# esp32.net
KiCad netlist of a schematic drawn in Altium Designer
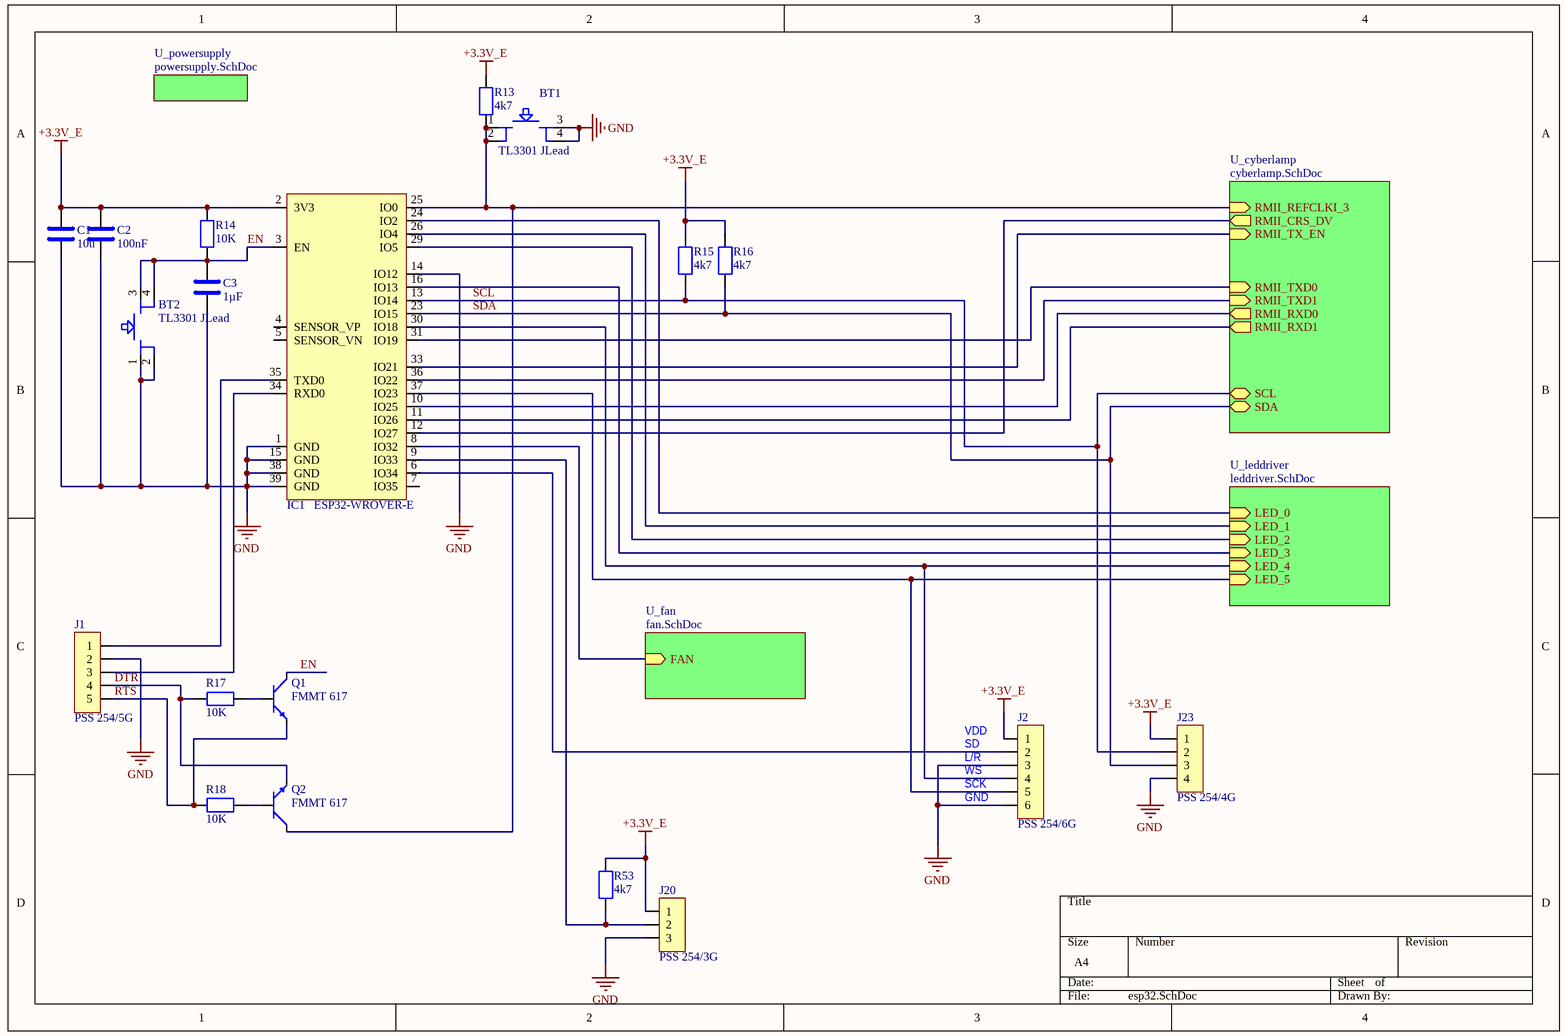
[diagram p0: esp32.SchDoc]

(export (version "E")
  (design (tool "Eeschema 10.0.6"))
  (components
    (comp (ref "BT1")
      (value "TL3301 JLead")
      (footprint "TL3301_Jlead")
      (description "TL3301 J-Lead button")
      (libsource (lib "switch_relais") (part "TK3301_jlead"))
    )
    (comp (ref "BT2")
      (value "TL3301 JLead")
      (footprint "TL3301_Jlead")
      (description "TL3301 J-Lead button")
      (libsource (lib "switch_relais") (part "TK3301_jlead"))
    )
    (comp (ref "C1")
      (value "10u")
      (footprint "1210")
      (description "10uF 63V X7R 1210")
      (fields (field (name "MOUSER PART") "81-GRM32ER71J106MA2L") (field (name "VOLTAGE") "63V"))
      (libsource (lib "capacitors") (part "10uF 63V X7R 1210"))
    )
    (comp (ref "C2")
      (value "100nF")
      (footprint "0603")
      (description "100nF 50V MLCC 0603")
      (fields (field (name "VOLTAGE") "50V"))
      (libsource (lib "capacitors") (part "100nF 50V MLCC 0603"))
    )
    (comp (ref "C3")
      (value "1µF")
      (footprint "0805")
      (description "1µF 25V MLCC 0805")
      (fields (field (name "VOLTAGE") "25V"))
      (libsource (lib "capacitor0805") (part "1µF 25V MLCC 0805"))
    )
    (comp (ref "IC1")
      (value "ESP32-WROVER-E")
      (footprint "ESP32-WROVER-I")
      (libsource (lib "microcontroller") (part "ESP32-WROVER-E-N16R2"))
    )
    (comp (ref "J1")
      (value "PSS 254/5G")
      (footprint "PSS 5pol")
      (description "PSS 5pol wire-to-board-connector")
      (libsource (lib "connectors_pss") (part "PSS 254/5G"))
    )
    (comp (ref "J2")
      (value "PSS 254/6G")
      (footprint "PSS 6pol")
      (description "PSS 6pol wire-to-board-connector")
      (libsource (lib "connectors_pss") (part "PSS 254/6G"))
    )
    (comp (ref "J20")
      (value "PSS 254/3G")
      (footprint "PSS 3pol")
      (description "PSS 3pol wire-to-board-connector")
      (libsource (lib "connectors_pss") (part "PSS 254/3G"))
    )
    (comp (ref "J23")
      (value "PSS 254/4G")
      (footprint "PSS 4pol")
      (description "PSS 4pol wire-to-board-connector")
      (libsource (lib "connectors_pss") (part "PSS 254/4G"))
    )
    (comp (ref "Q1")
      (value "FMMT 617")
      (footprint "SOT-23")
      (description "NPN switching Transistor, 3A")
      (libsource (lib "semiconductors") (part "FMMT 617"))
    )
    (comp (ref "Q2")
      (value "FMMT 617")
      (footprint "SOT-23")
      (description "NPN switching Transistor, 3A")
      (libsource (lib "semiconductors") (part "FMMT 617"))
    )
    (comp (ref "R13")
      (value "4k7")
      (footprint "res0603")
      (description "4k7 100mW 0603")
      (libsource (lib "resistors") (part "4k7 100mW 0603"))
    )
    (comp (ref "R14")
      (value "10K")
      (footprint "res0603")
      (description "10K 100mW 0603")
      (fields (field (name "TOLERANCE") "1%"))
      (libsource (lib "resistors") (part "10K 100mW 0603"))
    )
    (comp (ref "R15")
      (value "4k7")
      (footprint "res0603")
      (description "4k7 100mW 0603")
      (libsource (lib "resistors") (part "4k7 100mW 0603"))
    )
    (comp (ref "R16")
      (value "4k7")
      (footprint "res0603")
      (description "4k7 100mW 0603")
      (libsource (lib "resistors") (part "4k7 100mW 0603"))
    )
    (comp (ref "R17")
      (value "10K")
      (footprint "res0603")
      (description "10K 100mW 0603")
      (fields (field (name "TOLERANCE") "1%"))
      (libsource (lib "resistors") (part "10K 100mW 0603"))
    )
    (comp (ref "R18")
      (value "10K")
      (footprint "res0603")
      (description "10K 100mW 0603")
      (fields (field (name "TOLERANCE") "1%"))
      (libsource (lib "resistors") (part "10K 100mW 0603"))
    )
    (comp (ref "R53")
      (value "4k7")
      (footprint "res0603")
      (description "4k7 100mW 0603")
      (libsource (lib "resistors") (part "4k7 100mW 0603"))
    )
  )
  (nets
    (net (code "1") (name "+3.3V_E") (class "Default")
      (node (ref "C1") (pin "1") (pinfunction "1_1") (pintype "passive"))
      (node (ref "C2") (pin "1") (pinfunction "1_1") (pintype "passive"))
      (node (ref "IC1") (pin "2") (pinfunction "3V3_2") (pintype "passive"))
      (node (ref "J2") (pin "1") (pinfunction "1_1") (pintype "passive"))
      (node (ref "J20") (pin "1") (pinfunction "1_1") (pintype "passive"))
      (node (ref "J23") (pin "1") (pinfunction "1_1") (pintype "passive"))
      (node (ref "R13") (pin "2") (pinfunction "2_2") (pintype "passive"))
      (node (ref "R14") (pin "2") (pinfunction "2_2") (pintype "passive"))
      (node (ref "R15") (pin "2") (pinfunction "2_2") (pintype "passive"))
      (node (ref "R16") (pin "2") (pinfunction "2_2") (pintype "passive"))
      (node (ref "R53") (pin "2") (pinfunction "2_2") (pintype "passive"))
    )
    (net (code "2") (name "/DTR") (class "Default")
      (node (ref "J1") (pin "4") (pinfunction "4_4") (pintype "passive"))
      (node (ref "Q2") (pin "2") (pinfunction "2_2") (pintype "passive"))
      (node (ref "R17") (pin "2") (pinfunction "2_2") (pintype "passive"))
    )
    (net (code "3") (name "/EN") (class "Default")
      (node (ref "BT2") (pin "3") (pinfunction "3_3") (pintype "passive"))
      (node (ref "BT2") (pin "4") (pinfunction "4_4") (pintype "passive"))
      (node (ref "C3") (pin "1") (pinfunction "1_1") (pintype "passive"))
      (node (ref "IC1") (pin "3") (pinfunction "EN_3") (pintype "passive"))
      (node (ref "Q1") (pin "3") (pinfunction "3_3") (pintype "passive"))
      (node (ref "R14") (pin "1") (pinfunction "1_1") (pintype "passive"))
    )
    (net (code "4") (name "/FAN") (class "Default")
      (node (ref "IC1") (pin "8") (pinfunction "IO32_8") (pintype "passive"))
    )
    (net (code "5") (name "/LED_0") (class "Default")
      (node (ref "IC1") (pin "24") (pinfunction "IO2_24") (pintype "passive"))
    )
    (net (code "6") (name "/LED_1") (class "Default")
      (node (ref "IC1") (pin "26") (pinfunction "IO4_26") (pintype "passive"))
    )
    (net (code "7") (name "/LED_2") (class "Default")
      (node (ref "IC1") (pin "29") (pinfunction "IO5_29") (pintype "passive"))
    )
    (net (code "8") (name "/LED_3") (class "Default")
      (node (ref "IC1") (pin "16") (pinfunction "IO13_16") (pintype "passive"))
    )
    (net (code "9") (name "/LED_4") (class "Default")
      (node (ref "IC1") (pin "30") (pinfunction "IO18_30") (pintype "passive"))
      (node (ref "J2") (pin "4") (pinfunction "4_4") (pintype "passive"))
    )
    (net (code "10") (name "/LED_5") (class "Default")
      (node (ref "IC1") (pin "37") (pinfunction "IO23_37") (pintype "passive"))
      (node (ref "J2") (pin "5") (pinfunction "5_5") (pintype "passive"))
    )
    (net (code "11") (name "/RMII_CRS_DV") (class "Default")
      (node (ref "IC1") (pin "12") (pinfunction "IO27_12") (pintype "passive"))
    )
    (net (code "12") (name "/RMII_REFCLKI_3") (class "Default")
      (node (ref "BT1") (pin "1") (pinfunction "1_1") (pintype "passive"))
      (node (ref "BT1") (pin "2") (pinfunction "2_2") (pintype "passive"))
      (node (ref "IC1") (pin "25") (pinfunction "IO0_25") (pintype "passive"))
      (node (ref "Q2") (pin "3") (pinfunction "3_3") (pintype "passive"))
      (node (ref "R13") (pin "1") (pinfunction "1_1") (pintype "passive"))
    )
    (net (code "13") (name "/RMII_RXD0") (class "Default")
      (node (ref "IC1") (pin "10") (pinfunction "IO25_10") (pintype "passive"))
    )
    (net (code "14") (name "/RMII_RXD1") (class "Default")
      (node (ref "IC1") (pin "11") (pinfunction "IO26_11") (pintype "passive"))
    )
    (net (code "15") (name "/RMII_TXD0") (class "Default")
      (node (ref "IC1") (pin "31") (pinfunction "IO19_31") (pintype "passive"))
    )
    (net (code "16") (name "/RMII_TXD1") (class "Default")
      (node (ref "IC1") (pin "36") (pinfunction "IO22_36") (pintype "passive"))
    )
    (net (code "17") (name "/RMII_TX_EN") (class "Default")
      (node (ref "IC1") (pin "33") (pinfunction "IO21_33") (pintype "passive"))
    )
    (net (code "18") (name "/RTS") (class "Default")
      (node (ref "J1") (pin "5") (pinfunction "5_5") (pintype "passive"))
      (node (ref "Q1") (pin "2") (pinfunction "2_2") (pintype "passive"))
      (node (ref "R18") (pin "2") (pinfunction "2_2") (pintype "passive"))
    )
    (net (code "19") (name "/SCL") (class "Default")
      (node (ref "IC1") (pin "13") (pinfunction "IO14_13") (pintype "passive"))
      (node (ref "J23") (pin "2") (pinfunction "2_2") (pintype "passive"))
      (node (ref "R15") (pin "1") (pinfunction "1_1") (pintype "passive"))
    )
    (net (code "20") (name "/SDA") (class "Default")
      (node (ref "IC1") (pin "23") (pinfunction "IO15_23") (pintype "passive"))
      (node (ref "J23") (pin "3") (pinfunction "3_3") (pintype "passive"))
      (node (ref "R16") (pin "1") (pinfunction "1_1") (pintype "passive"))
    )
    (net (code "21") (name "GND") (class "Default")
      (node (ref "BT1") (pin "3") (pinfunction "3_3") (pintype "passive"))
      (node (ref "BT1") (pin "4") (pinfunction "4_4") (pintype "passive"))
      (node (ref "BT2") (pin "1") (pinfunction "1_1") (pintype "passive"))
      (node (ref "BT2") (pin "2") (pinfunction "2_2") (pintype "passive"))
      (node (ref "C1") (pin "2") (pinfunction "2_2") (pintype "passive"))
      (node (ref "C2") (pin "2") (pinfunction "2_2") (pintype "passive"))
      (node (ref "C3") (pin "2") (pinfunction "2_2") (pintype "passive"))
      (node (ref "IC1") (pin "1") (pinfunction "GND_1") (pintype "passive"))
      (node (ref "IC1") (pin "14") (pinfunction "IO12_14") (pintype "passive"))
      (node (ref "IC1") (pin "15") (pinfunction "GND_15") (pintype "passive"))
      (node (ref "IC1") (pin "38") (pinfunction "GND_38") (pintype "passive"))
      (node (ref "IC1") (pin "39") (pinfunction "GND_39") (pintype "passive"))
      (node (ref "J1") (pin "2") (pinfunction "2_2") (pintype "passive"))
      (node (ref "J2") (pin "3") (pinfunction "3_3") (pintype "passive"))
      (node (ref "J2") (pin "6") (pinfunction "6_6") (pintype "passive"))
      (node (ref "J20") (pin "3") (pinfunction "3_3") (pintype "passive"))
      (node (ref "J23") (pin "4") (pinfunction "4_4") (pintype "passive"))
    )
    (net (code "22") (name "Net-(IC1-IO33)") (class "Default")
      (node (ref "IC1") (pin "9") (pinfunction "IO33_9") (pintype "passive"))
      (node (ref "J20") (pin "2") (pinfunction "2_2") (pintype "passive"))
      (node (ref "R53") (pin "1") (pinfunction "1_1") (pintype "passive"))
    )
    (net (code "23") (name "Net-(IC1-IO34)") (class "Default")
      (node (ref "IC1") (pin "6") (pinfunction "IO34_6") (pintype "passive"))
      (node (ref "J2") (pin "2") (pinfunction "2_2") (pintype "passive"))
    )
    (net (code "24") (name "Net-(IC1-RXD0)") (class "Default")
      (node (ref "IC1") (pin "34") (pinfunction "RXD0_34") (pintype "passive"))
      (node (ref "J1") (pin "3") (pinfunction "3_3") (pintype "passive"))
    )
    (net (code "25") (name "Net-(IC1-TXD0)") (class "Default")
      (node (ref "IC1") (pin "35") (pinfunction "TXD0_35") (pintype "passive"))
      (node (ref "J1") (pin "1") (pinfunction "1_1") (pintype "passive"))
    )
    (net (code "26") (name "Net-(Q1-Pad1)") (class "Default")
      (node (ref "Q1") (pin "1") (pinfunction "1_1") (pintype "passive"))
      (node (ref "R17") (pin "1") (pinfunction "1_1") (pintype "passive"))
    )
    (net (code "27") (name "Net-(Q2-Pad1)") (class "Default")
      (node (ref "Q2") (pin "1") (pinfunction "1_1") (pintype "passive"))
      (node (ref "R18") (pin "1") (pinfunction "1_1") (pintype "passive"))
    )
    (net (code "28") (name "unconnected-(IC1-IO35-Pad7)") (class "Default")
      (node (ref "IC1") (pin "7") (pinfunction "IO35_7") (pintype "passive"))
    )
    (net (code "29") (name "unconnected-(IC1-SENSOR_VN-Pad5)") (class "Default")
      (node (ref "IC1") (pin "5") (pinfunction "SENSOR_VN_5") (pintype "passive"))
    )
    (net (code "30") (name "unconnected-(IC1-SENSOR_VP-Pad4)") (class "Default")
      (node (ref "IC1") (pin "4") (pinfunction "SENSOR_VP_4") (pintype "passive"))
    )
  )
)
